# V2.net
KiCad netlist of a schematic drawn in Altium Designer
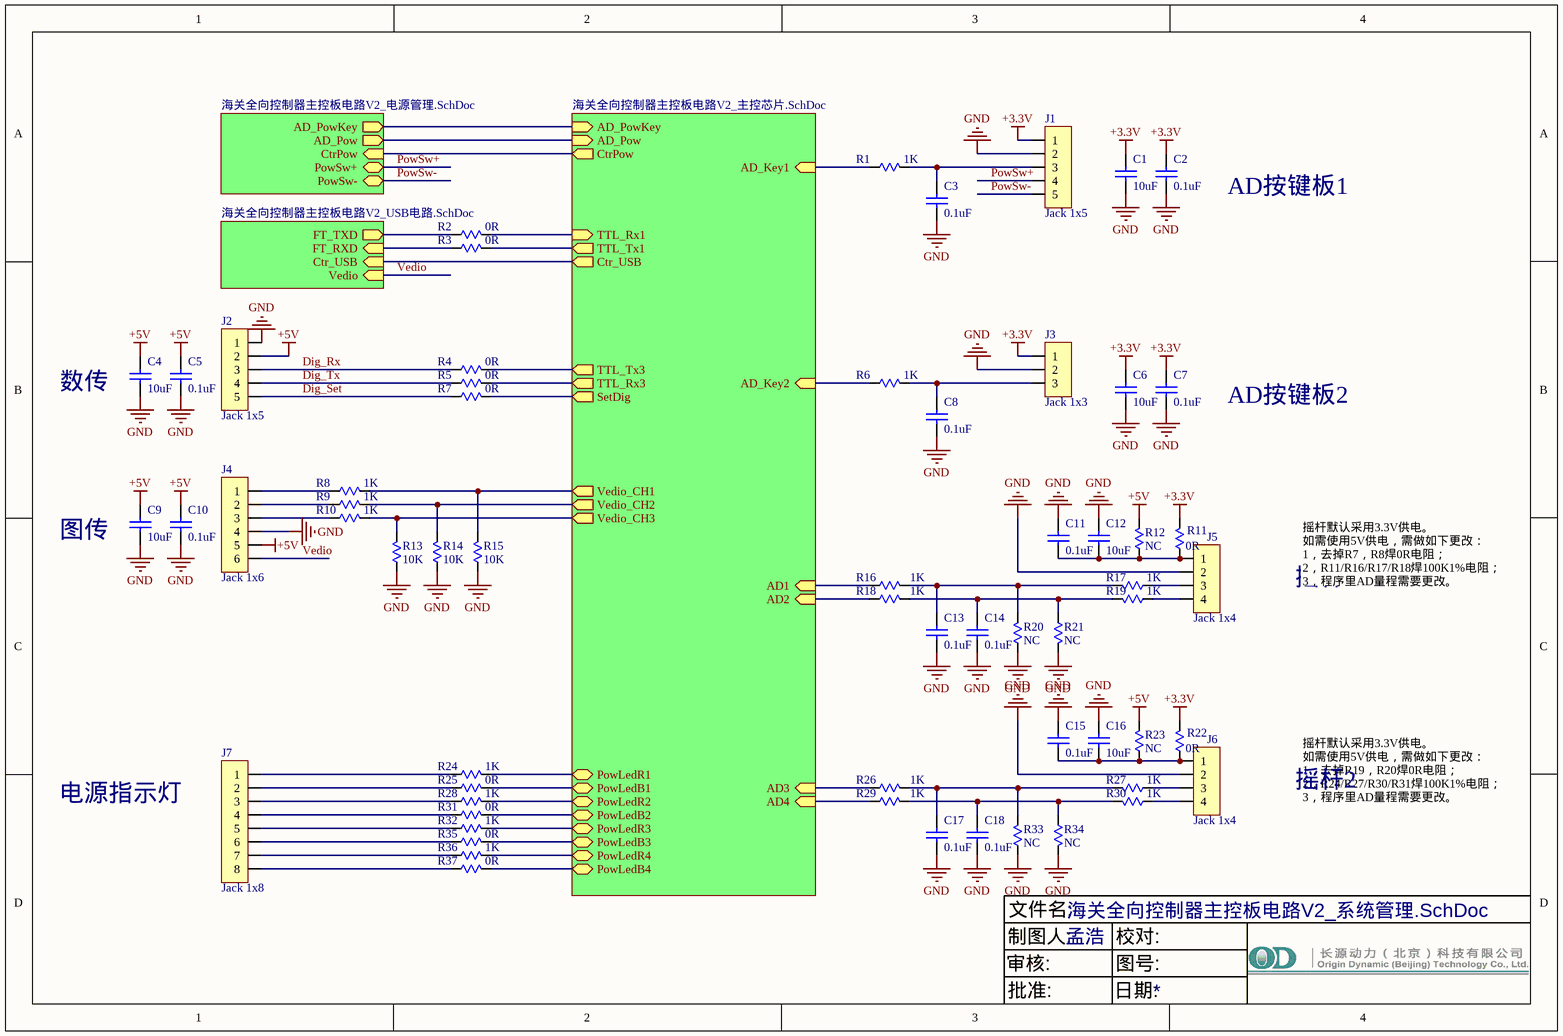
[diagram p0: 海关全向控制器主控板电路V2_系统管理.SchDoc]

(export (version "E")
  (design (tool "Eeschema 10.0.6"))
  (components
    (comp (ref "C1")
      (value "10uF")
      (footprint "C0603")
      (description "Capacitor")
      (fields (field (name "PUBLISHER") "Altium Limited"))
      (libsource (lib "Miscellaneous Devices") (part "Cap"))
    )
    (comp (ref "C2")
      (value "0.1uF")
      (footprint "C0603")
      (description "Capacitor")
      (fields (field (name "PUBLISHER") "Altium Limited"))
      (libsource (lib "Miscellaneous Devices") (part "Cap"))
    )
    (comp (ref "C3")
      (value "0.1uF")
      (footprint "C0603")
      (description "Capacitor")
      (fields (field (name "PUBLISHER") "Altium Limited"))
      (libsource (lib "Miscellaneous Devices") (part "Cap"))
    )
    (comp (ref "C4")
      (value "10uF")
      (footprint "C0603")
      (description "Capacitor")
      (fields (field (name "PUBLISHER") "Altium Limited"))
      (libsource (lib "Miscellaneous Devices") (part "Cap"))
    )
    (comp (ref "C5")
      (value "0.1uF")
      (footprint "C0603")
      (description "Capacitor")
      (fields (field (name "PUBLISHER") "Altium Limited"))
      (libsource (lib "Miscellaneous Devices") (part "Cap"))
    )
    (comp (ref "C6")
      (value "10uF")
      (footprint "C0603")
      (description "Capacitor")
      (fields (field (name "PUBLISHER") "Altium Limited"))
      (libsource (lib "Miscellaneous Devices") (part "Cap"))
    )
    (comp (ref "C7")
      (value "0.1uF")
      (footprint "C0603")
      (description "Capacitor")
      (fields (field (name "PUBLISHER") "Altium Limited"))
      (libsource (lib "Miscellaneous Devices") (part "Cap"))
    )
    (comp (ref "C8")
      (value "0.1uF")
      (footprint "C0603")
      (description "Capacitor")
      (fields (field (name "PUBLISHER") "Altium Limited"))
      (libsource (lib "Miscellaneous Devices") (part "Cap"))
    )
    (comp (ref "C9")
      (value "10uF")
      (footprint "C0603")
      (description "Capacitor")
      (fields (field (name "PUBLISHER") "Altium Limited"))
      (libsource (lib "Miscellaneous Devices") (part "Cap"))
    )
    (comp (ref "C10")
      (value "0.1uF")
      (footprint "C0603")
      (description "Capacitor")
      (fields (field (name "PUBLISHER") "Altium Limited"))
      (libsource (lib "Miscellaneous Devices") (part "Cap"))
    )
    (comp (ref "C11")
      (value "0.1uF")
      (footprint "C0603")
      (description "Capacitor")
      (fields (field (name "PUBLISHER") "Altium Limited"))
      (libsource (lib "Miscellaneous Devices") (part "Cap"))
    )
    (comp (ref "C12")
      (value "10uF")
      (footprint "C0603")
      (description "Capacitor")
      (fields (field (name "PUBLISHER") "Altium Limited"))
      (libsource (lib "Miscellaneous Devices") (part "Cap"))
    )
    (comp (ref "C13")
      (value "0.1uF")
      (footprint "C0603")
      (description "Capacitor")
      (fields (field (name "PUBLISHER") "Altium Limited"))
      (libsource (lib "Miscellaneous Devices") (part "Cap"))
    )
    (comp (ref "C14")
      (value "0.1uF")
      (footprint "C0603")
      (description "Capacitor")
      (fields (field (name "PUBLISHER") "Altium Limited"))
      (libsource (lib "Miscellaneous Devices") (part "Cap"))
    )
    (comp (ref "C15")
      (value "0.1uF")
      (footprint "C0603")
      (description "Capacitor")
      (fields (field (name "PUBLISHER") "Altium Limited"))
      (libsource (lib "Miscellaneous Devices") (part "Cap"))
    )
    (comp (ref "C16")
      (value "10uF")
      (footprint "C0603")
      (description "Capacitor")
      (fields (field (name "PUBLISHER") "Altium Limited"))
      (libsource (lib "Miscellaneous Devices") (part "Cap"))
    )
    (comp (ref "C17")
      (value "0.1uF")
      (footprint "C0603")
      (description "Capacitor")
      (fields (field (name "PUBLISHER") "Altium Limited"))
      (libsource (lib "Miscellaneous Devices") (part "Cap"))
    )
    (comp (ref "C18")
      (value "0.1uF")
      (footprint "C0603")
      (description "Capacitor")
      (fields (field (name "PUBLISHER") "Altium Limited"))
      (libsource (lib "Miscellaneous Devices") (part "Cap"))
    )
    (comp (ref "J1")
      (value "Jack 1x5")
      (footprint "ZH-5AWD")
      (description "插座")
      (libsource (lib "Connector") (part "Jack 1x5"))
    )
    (comp (ref "J2")
      (value "Jack 1x5")
      (footprint "ZH-5AWD")
      (description "插座")
      (libsource (lib "") (part "Jack 1x5_1"))
    )
    (comp (ref "J3")
      (value "Jack 1x3")
      (footprint "ZH-3AWD")
      (description "插座")
      (libsource (lib "Connector") (part "Jack 1x3"))
    )
    (comp (ref "J4")
      (value "Jack 1x6")
      (footprint "ZH-6AWD")
      (description "插座")
      (libsource (lib "Connector") (part "Jack 1x6"))
    )
    (comp (ref "J5")
      (value "Jack 1x4")
      (footprint "ZH-4AWD")
      (description "插座")
      (libsource (lib "Connector") (part "Jack 1x4"))
    )
    (comp (ref "J6")
      (value "Jack 1x4")
      (footprint "ZH-4AWD")
      (description "插座")
      (libsource (lib "Connector") (part "Jack 1x4"))
    )
    (comp (ref "J7")
      (value "Jack 1x8")
      (footprint "ZH-8AWD")
      (description "插座")
      (libsource (lib "Connector") (part "Jack 1x8"))
    )
    (comp (ref "R1")
      (value "1K")
      (footprint "R0603")
      (description "Resistor")
      (fields (field (name "PUBLISHER") "Altium Limited"))
      (libsource (lib "UP-Robot") (part "Res"))
    )
    (comp (ref "R2")
      (value "0R")
      (footprint "R0603")
      (description "Resistor")
      (fields (field (name "PUBLISHER") "Altium Limited"))
      (libsource (lib "Temp") (part "Res"))
    )
    (comp (ref "R3")
      (value "0R")
      (footprint "R0603")
      (description "Resistor")
      (fields (field (name "PUBLISHER") "Altium Limited"))
      (libsource (lib "Temp") (part "Res"))
    )
    (comp (ref "R4")
      (value "0R")
      (footprint "R0603")
      (description "Resistor")
      (fields (field (name "PUBLISHER") "Altium Limited"))
      (libsource (lib "UP-Robot") (part "Res"))
    )
    (comp (ref "R5")
      (value "0R")
      (footprint "R0603")
      (description "Resistor")
      (fields (field (name "PUBLISHER") "Altium Limited"))
      (libsource (lib "UP-Robot") (part "Res"))
    )
    (comp (ref "R6")
      (value "1K")
      (footprint "R0603")
      (description "Resistor")
      (fields (field (name "PUBLISHER") "Altium Limited"))
      (libsource (lib "UP-Robot") (part "Res"))
    )
    (comp (ref "R7")
      (value "0R")
      (footprint "R0603")
      (description "Resistor")
      (fields (field (name "PUBLISHER") "Altium Limited"))
      (libsource (lib "UP-Robot") (part "Res"))
    )
    (comp (ref "R8")
      (value "1K")
      (footprint "R0603")
      (description "Resistor")
      (fields (field (name "PUBLISHER") "Altium Limited"))
      (libsource (lib "UP-Robot") (part "Res"))
    )
    (comp (ref "R9")
      (value "1K")
      (footprint "R0603")
      (description "Resistor")
      (fields (field (name "PUBLISHER") "Altium Limited"))
      (libsource (lib "UP-Robot") (part "Res"))
    )
    (comp (ref "R10")
      (value "1K")
      (footprint "R0603")
      (description "Resistor")
      (fields (field (name "PUBLISHER") "Altium Limited"))
      (libsource (lib "UP-Robot") (part "Res"))
    )
    (comp (ref "R11")
      (value "0R")
      (footprint "R0603")
      (description "Resistor")
      (fields (field (name "PUBLISHER") "Altium Limited"))
      (libsource (lib "UP-Robot") (part "Res"))
    )
    (comp (ref "R12")
      (value "NC")
      (footprint "R0603")
      (description "Resistor")
      (fields (field (name "PUBLISHER") "Altium Limited"))
      (libsource (lib "UP-Robot") (part "Res"))
    )
    (comp (ref "R13")
      (value "10K")
      (footprint "R0603")
      (description "Resistor")
      (fields (field (name "PUBLISHER") "Altium Limited"))
      (libsource (lib "UP-Robot") (part "Res"))
    )
    (comp (ref "R14")
      (value "10K")
      (footprint "R0603")
      (description "Resistor")
      (fields (field (name "PUBLISHER") "Altium Limited"))
      (libsource (lib "UP-Robot") (part "Res"))
    )
    (comp (ref "R15")
      (value "10K")
      (footprint "R0603")
      (description "Resistor")
      (fields (field (name "PUBLISHER") "Altium Limited"))
      (libsource (lib "UP-Robot") (part "Res"))
    )
    (comp (ref "R16")
      (value "1K")
      (footprint "R0603")
      (description "Resistor")
      (fields (field (name "PUBLISHER") "Altium Limited"))
      (libsource (lib "UP-Robot") (part "Res"))
    )
    (comp (ref "R17")
      (value "1K")
      (footprint "R0603")
      (description "Resistor")
      (fields (field (name "PUBLISHER") "Altium Limited"))
      (libsource (lib "UP-Robot") (part "Res"))
    )
    (comp (ref "R18")
      (value "1K")
      (footprint "R0603")
      (description "Resistor")
      (fields (field (name "PUBLISHER") "Altium Limited"))
      (libsource (lib "UP-Robot") (part "Res"))
    )
    (comp (ref "R19")
      (value "1K")
      (footprint "R0603")
      (description "Resistor")
      (fields (field (name "PUBLISHER") "Altium Limited"))
      (libsource (lib "UP-Robot") (part "Res"))
    )
    (comp (ref "R20")
      (value "NC")
      (footprint "R0603")
      (description "Resistor")
      (fields (field (name "PUBLISHER") "Altium Limited"))
      (libsource (lib "UP-Robot") (part "Res"))
    )
    (comp (ref "R21")
      (value "NC")
      (footprint "R0603")
      (description "Resistor")
      (fields (field (name "PUBLISHER") "Altium Limited"))
      (libsource (lib "UP-Robot") (part "Res"))
    )
    (comp (ref "R22")
      (value "0R")
      (footprint "R0603")
      (description "Resistor")
      (fields (field (name "PUBLISHER") "Altium Limited"))
      (libsource (lib "UP-Robot") (part "Res"))
    )
    (comp (ref "R23")
      (value "NC")
      (footprint "R0603")
      (description "Resistor")
      (fields (field (name "PUBLISHER") "Altium Limited"))
      (libsource (lib "UP-Robot") (part "Res"))
    )
    (comp (ref "R24")
      (value "1K")
      (footprint "R0603")
      (description "Resistor")
      (fields (field (name "PUBLISHER") "Altium Limited"))
      (libsource (lib "UP-Robot") (part "Res"))
    )
    (comp (ref "R25")
      (value "0R")
      (footprint "R0603")
      (description "Resistor")
      (fields (field (name "PUBLISHER") "Altium Limited"))
      (libsource (lib "UP-Robot") (part "Res"))
    )
    (comp (ref "R26")
      (value "1K")
      (footprint "R0603")
      (description "Resistor")
      (fields (field (name "PUBLISHER") "Altium Limited"))
      (libsource (lib "UP-Robot") (part "Res"))
    )
    (comp (ref "R27")
      (value "1K")
      (footprint "R0603")
      (description "Resistor")
      (fields (field (name "PUBLISHER") "Altium Limited"))
      (libsource (lib "UP-Robot") (part "Res"))
    )
    (comp (ref "R28")
      (value "1K")
      (footprint "R0603")
      (description "Resistor")
      (fields (field (name "PUBLISHER") "Altium Limited"))
      (libsource (lib "UP-Robot") (part "Res"))
    )
    (comp (ref "R29")
      (value "1K")
      (footprint "R0603")
      (description "Resistor")
      (fields (field (name "PUBLISHER") "Altium Limited"))
      (libsource (lib "UP-Robot") (part "Res"))
    )
    (comp (ref "R30")
      (value "1K")
      (footprint "R0603")
      (description "Resistor")
      (fields (field (name "PUBLISHER") "Altium Limited"))
      (libsource (lib "UP-Robot") (part "Res"))
    )
    (comp (ref "R31")
      (value "0R")
      (footprint "R0603")
      (description "Resistor")
      (fields (field (name "PUBLISHER") "Altium Limited"))
      (libsource (lib "UP-Robot") (part "Res"))
    )
    (comp (ref "R32")
      (value "1K")
      (footprint "R0603")
      (description "Resistor")
      (fields (field (name "PUBLISHER") "Altium Limited"))
      (libsource (lib "UP-Robot") (part "Res"))
    )
    (comp (ref "R33")
      (value "NC")
      (footprint "R0603")
      (description "Resistor")
      (fields (field (name "PUBLISHER") "Altium Limited"))
      (libsource (lib "UP-Robot") (part "Res"))
    )
    (comp (ref "R34")
      (value "NC")
      (footprint "R0603")
      (description "Resistor")
      (fields (field (name "PUBLISHER") "Altium Limited"))
      (libsource (lib "UP-Robot") (part "Res"))
    )
    (comp (ref "R35")
      (value "0R")
      (footprint "R0603")
      (description "Resistor")
      (fields (field (name "PUBLISHER") "Altium Limited"))
      (libsource (lib "UP-Robot") (part "Res"))
    )
    (comp (ref "R36")
      (value "1K")
      (footprint "R0603")
      (description "Resistor")
      (fields (field (name "PUBLISHER") "Altium Limited"))
      (libsource (lib "UP-Robot") (part "Res"))
    )
    (comp (ref "R37")
      (value "0R")
      (footprint "R0603")
      (description "Resistor")
      (fields (field (name "PUBLISHER") "Altium Limited"))
      (libsource (lib "UP-Robot") (part "Res"))
    )
  )
  (nets
    (net (code "1") (name "+3.3V") (class "Default")
      (node (ref "C1") (pin "1") (pinfunction "1_1") (pintype "passive"))
      (node (ref "C2") (pin "1") (pinfunction "1_1") (pintype "passive"))
      (node (ref "C6") (pin "1") (pinfunction "1_1") (pintype "passive"))
      (node (ref "C7") (pin "1") (pinfunction "1_1") (pintype "passive"))
      (node (ref "J1") (pin "1") (pinfunction "1_1") (pintype "passive"))
      (node (ref "J3") (pin "1") (pinfunction "1_1") (pintype "passive"))
      (node (ref "R11") (pin "1") (pinfunction "1_1") (pintype "passive"))
      (node (ref "R22") (pin "1") (pinfunction "1_1") (pintype "passive"))
    )
    (net (code "2") (name "+5V") (class "Default")
      (node (ref "C10") (pin "1") (pinfunction "1_1") (pintype "passive"))
      (node (ref "C4") (pin "1") (pinfunction "1_1") (pintype "passive"))
      (node (ref "C5") (pin "1") (pinfunction "1_1") (pintype "passive"))
      (node (ref "C9") (pin "1") (pinfunction "1_1") (pintype "passive"))
      (node (ref "J2") (pin "2") (pinfunction "2_2") (pintype "passive"))
      (node (ref "J4") (pin "5") (pinfunction "5_5") (pintype "passive"))
      (node (ref "R12") (pin "1") (pinfunction "1_1") (pintype "passive"))
      (node (ref "R23") (pin "1") (pinfunction "1_1") (pintype "passive"))
    )
    (net (code "3") (name "/AD1") (class "Default")
      (node (ref "R16") (pin "2") (pinfunction "2_2") (pintype "passive"))
    )
    (net (code "4") (name "/AD2") (class "Default")
      (node (ref "R18") (pin "2") (pinfunction "2_2") (pintype "passive"))
    )
    (net (code "5") (name "/AD3") (class "Default")
      (node (ref "R26") (pin "2") (pinfunction "2_2") (pintype "passive"))
    )
    (net (code "6") (name "/AD4") (class "Default")
      (node (ref "R29") (pin "2") (pinfunction "2_2") (pintype "passive"))
    )
    (net (code "7") (name "/AD_Key1") (class "Default")
      (node (ref "R1") (pin "1") (pinfunction "1_1") (pintype "passive"))
    )
    (net (code "8") (name "/AD_Key2") (class "Default")
      (node (ref "R6") (pin "1") (pinfunction "1_1") (pintype "passive"))
    )
    (net (code "13") (name "/Dig_Rx") (class "Default")
      (node (ref "J2") (pin "3") (pinfunction "3_3") (pintype "passive"))
      (node (ref "R4") (pin "1") (pinfunction "1_1") (pintype "passive"))
    )
    (net (code "14") (name "/Dig_Set") (class "Default")
      (node (ref "J2") (pin "5") (pinfunction "5_5") (pintype "passive"))
      (node (ref "R7") (pin "1") (pinfunction "1_1") (pintype "passive"))
    )
    (net (code "15") (name "/Dig_Tx") (class "Default")
      (node (ref "J2") (pin "4") (pinfunction "4_4") (pintype "passive"))
      (node (ref "R5") (pin "1") (pinfunction "1_1") (pintype "passive"))
    )
    (net (code "16") (name "/FT_RXD") (class "Default")
      (node (ref "R3") (pin "2") (pinfunction "2_2") (pintype "passive"))
    )
    (net (code "17") (name "/FT_TXD") (class "Default")
      (node (ref "R2") (pin "2") (pinfunction "2_2") (pintype "passive"))
    )
    (net (code "18") (name "/PowLedB1") (class "Default")
      (node (ref "R25") (pin "2") (pinfunction "2_2") (pintype "passive"))
    )
    (net (code "19") (name "/PowLedB2") (class "Default")
      (node (ref "R31") (pin "2") (pinfunction "2_2") (pintype "passive"))
    )
    (net (code "20") (name "/PowLedB3") (class "Default")
      (node (ref "R35") (pin "2") (pinfunction "2_2") (pintype "passive"))
    )
    (net (code "21") (name "/PowLedB4") (class "Default")
      (node (ref "R37") (pin "2") (pinfunction "2_2") (pintype "passive"))
    )
    (net (code "22") (name "/PowLedR1") (class "Default")
      (node (ref "R24") (pin "2") (pinfunction "2_2") (pintype "passive"))
    )
    (net (code "23") (name "/PowLedR2") (class "Default")
      (node (ref "R28") (pin "2") (pinfunction "2_2") (pintype "passive"))
    )
    (net (code "24") (name "/PowLedR3") (class "Default")
      (node (ref "R32") (pin "2") (pinfunction "2_2") (pintype "passive"))
    )
    (net (code "25") (name "/PowLedR4") (class "Default")
      (node (ref "R36") (pin "2") (pinfunction "2_2") (pintype "passive"))
    )
    (net (code "26") (name "/PowSw+") (class "Default")
      (node (ref "J1") (pin "4") (pinfunction "4_4") (pintype "passive"))
    )
    (net (code "27") (name "/PowSw-") (class "Default")
      (node (ref "J1") (pin "5") (pinfunction "5_5") (pintype "passive"))
    )
    (net (code "28") (name "/SetDig") (class "Default")
      (node (ref "R7") (pin "2") (pinfunction "2_2") (pintype "passive"))
    )
    (net (code "29") (name "/TTL_Rx1") (class "Default")
      (node (ref "R2") (pin "1") (pinfunction "1_1") (pintype "passive"))
    )
    (net (code "30") (name "/TTL_Rx3") (class "Default")
      (node (ref "R5") (pin "2") (pinfunction "2_2") (pintype "passive"))
    )
    (net (code "31") (name "/TTL_Tx1") (class "Default")
      (node (ref "R3") (pin "1") (pinfunction "1_1") (pintype "passive"))
    )
    (net (code "32") (name "/TTL_Tx3") (class "Default")
      (node (ref "R4") (pin "2") (pinfunction "2_2") (pintype "passive"))
    )
    (net (code "33") (name "/Vedio") (class "Default")
      (node (ref "J4") (pin "6") (pinfunction "6_6") (pintype "passive"))
    )
    (net (code "34") (name "/Vedio_CH1") (class "Default")
      (node (ref "R15") (pin "2") (pinfunction "2_2") (pintype "passive"))
      (node (ref "R8") (pin "2") (pinfunction "2_2") (pintype "passive"))
    )
    (net (code "35") (name "/Vedio_CH2") (class "Default")
      (node (ref "R14") (pin "2") (pinfunction "2_2") (pintype "passive"))
      (node (ref "R9") (pin "2") (pinfunction "2_2") (pintype "passive"))
    )
    (net (code "36") (name "/Vedio_CH3") (class "Default")
      (node (ref "R10") (pin "2") (pinfunction "2_2") (pintype "passive"))
      (node (ref "R13") (pin "2") (pinfunction "2_2") (pintype "passive"))
    )
    (net (code "37") (name "GND") (class "Default")
      (node (ref "C1") (pin "2") (pinfunction "2_2") (pintype "passive"))
      (node (ref "C10") (pin "2") (pinfunction "2_2") (pintype "passive"))
      (node (ref "C11") (pin "1") (pinfunction "1_1") (pintype "passive"))
      (node (ref "C12") (pin "1") (pinfunction "1_1") (pintype "passive"))
      (node (ref "C13") (pin "2") (pinfunction "2_2") (pintype "passive"))
      (node (ref "C14") (pin "2") (pinfunction "2_2") (pintype "passive"))
      (node (ref "C15") (pin "1") (pinfunction "1_1") (pintype "passive"))
      (node (ref "C16") (pin "1") (pinfunction "1_1") (pintype "passive"))
      (node (ref "C17") (pin "2") (pinfunction "2_2") (pintype "passive"))
      (node (ref "C18") (pin "2") (pinfunction "2_2") (pintype "passive"))
      (node (ref "C2") (pin "2") (pinfunction "2_2") (pintype "passive"))
      (node (ref "C3") (pin "2") (pinfunction "2_2") (pintype "passive"))
      (node (ref "C4") (pin "2") (pinfunction "2_2") (pintype "passive"))
      (node (ref "C5") (pin "2") (pinfunction "2_2") (pintype "passive"))
      (node (ref "C6") (pin "2") (pinfunction "2_2") (pintype "passive"))
      (node (ref "C7") (pin "2") (pinfunction "2_2") (pintype "passive"))
      (node (ref "C8") (pin "2") (pinfunction "2_2") (pintype "passive"))
      (node (ref "C9") (pin "2") (pinfunction "2_2") (pintype "passive"))
      (node (ref "J1") (pin "2") (pinfunction "2_2") (pintype "passive"))
      (node (ref "J2") (pin "1") (pinfunction "1_1") (pintype "passive"))
      (node (ref "J3") (pin "2") (pinfunction "2_2") (pintype "passive"))
      (node (ref "J4") (pin "4") (pinfunction "4_4") (pintype "passive"))
      (node (ref "J5") (pin "2") (pinfunction "2_2") (pintype "passive"))
      (node (ref "J6") (pin "2") (pinfunction "2_2") (pintype "passive"))
      (node (ref "R13") (pin "1") (pinfunction "1_1") (pintype "passive"))
      (node (ref "R14") (pin "1") (pinfunction "1_1") (pintype "passive"))
      (node (ref "R15") (pin "1") (pinfunction "1_1") (pintype "passive"))
      (node (ref "R20") (pin "2") (pinfunction "2_2") (pintype "passive"))
      (node (ref "R21") (pin "1") (pinfunction "1_1") (pintype "passive"))
      (node (ref "R33") (pin "2") (pinfunction "2_2") (pintype "passive"))
      (node (ref "R34") (pin "1") (pinfunction "1_1") (pintype "passive"))
    )
    (net (code "38") (name "Net-(C3-Pad1)") (class "Default")
      (node (ref "C3") (pin "1") (pinfunction "1_1") (pintype "passive"))
      (node (ref "J1") (pin "3") (pinfunction "3_3") (pintype "passive"))
      (node (ref "R1") (pin "2") (pinfunction "2_2") (pintype "passive"))
    )
    (net (code "39") (name "Net-(C8-Pad1)") (class "Default")
      (node (ref "C8") (pin "1") (pinfunction "1_1") (pintype "passive"))
      (node (ref "J3") (pin "3") (pinfunction "3_3") (pintype "passive"))
      (node (ref "R6") (pin "2") (pinfunction "2_2") (pintype "passive"))
    )
    (net (code "40") (name "Net-(C11-Pad2)") (class "Default")
      (node (ref "C11") (pin "2") (pinfunction "2_2") (pintype "passive"))
      (node (ref "C12") (pin "2") (pinfunction "2_2") (pintype "passive"))
      (node (ref "J5") (pin "1") (pinfunction "1_1") (pintype "passive"))
      (node (ref "R11") (pin "2") (pinfunction "2_2") (pintype "passive"))
      (node (ref "R12") (pin "2") (pinfunction "2_2") (pintype "passive"))
    )
    (net (code "41") (name "Net-(C13-Pad1)") (class "Default")
      (node (ref "C13") (pin "1") (pinfunction "1_1") (pintype "passive"))
      (node (ref "R16") (pin "1") (pinfunction "1_1") (pintype "passive"))
      (node (ref "R17") (pin "1") (pinfunction "1_1") (pintype "passive"))
      (node (ref "R20") (pin "1") (pinfunction "1_1") (pintype "passive"))
    )
    (net (code "42") (name "Net-(C14-Pad1)") (class "Default")
      (node (ref "C14") (pin "1") (pinfunction "1_1") (pintype "passive"))
      (node (ref "R18") (pin "1") (pinfunction "1_1") (pintype "passive"))
      (node (ref "R19") (pin "1") (pinfunction "1_1") (pintype "passive"))
      (node (ref "R21") (pin "2") (pinfunction "2_2") (pintype "passive"))
    )
    (net (code "43") (name "Net-(C15-Pad2)") (class "Default")
      (node (ref "C15") (pin "2") (pinfunction "2_2") (pintype "passive"))
      (node (ref "C16") (pin "2") (pinfunction "2_2") (pintype "passive"))
      (node (ref "J6") (pin "1") (pinfunction "1_1") (pintype "passive"))
      (node (ref "R22") (pin "2") (pinfunction "2_2") (pintype "passive"))
      (node (ref "R23") (pin "2") (pinfunction "2_2") (pintype "passive"))
    )
    (net (code "44") (name "Net-(C17-Pad1)") (class "Default")
      (node (ref "C17") (pin "1") (pinfunction "1_1") (pintype "passive"))
      (node (ref "R26") (pin "1") (pinfunction "1_1") (pintype "passive"))
      (node (ref "R27") (pin "1") (pinfunction "1_1") (pintype "passive"))
      (node (ref "R33") (pin "1") (pinfunction "1_1") (pintype "passive"))
    )
    (net (code "45") (name "Net-(C18-Pad1)") (class "Default")
      (node (ref "C18") (pin "1") (pinfunction "1_1") (pintype "passive"))
      (node (ref "R29") (pin "1") (pinfunction "1_1") (pintype "passive"))
      (node (ref "R30") (pin "1") (pinfunction "1_1") (pintype "passive"))
      (node (ref "R34") (pin "2") (pinfunction "2_2") (pintype "passive"))
    )
    (net (code "46") (name "Net-(J4-Pad1)") (class "Default")
      (node (ref "J4") (pin "1") (pinfunction "1_1") (pintype "passive"))
      (node (ref "R8") (pin "1") (pinfunction "1_1") (pintype "passive"))
    )
    (net (code "47") (name "Net-(J4-Pad2)") (class "Default")
      (node (ref "J4") (pin "2") (pinfunction "2_2") (pintype "passive"))
      (node (ref "R9") (pin "1") (pinfunction "1_1") (pintype "passive"))
    )
    (net (code "48") (name "Net-(J4-Pad3)") (class "Default")
      (node (ref "J4") (pin "3") (pinfunction "3_3") (pintype "passive"))
      (node (ref "R10") (pin "1") (pinfunction "1_1") (pintype "passive"))
    )
    (net (code "49") (name "Net-(J5-Pad3)") (class "Default")
      (node (ref "J5") (pin "3") (pinfunction "3_3") (pintype "passive"))
      (node (ref "R17") (pin "2") (pinfunction "2_2") (pintype "passive"))
    )
    (net (code "50") (name "Net-(J5-Pad4)") (class "Default")
      (node (ref "J5") (pin "4") (pinfunction "4_4") (pintype "passive"))
      (node (ref "R19") (pin "2") (pinfunction "2_2") (pintype "passive"))
    )
    (net (code "51") (name "Net-(J6-Pad3)") (class "Default")
      (node (ref "J6") (pin "3") (pinfunction "3_3") (pintype "passive"))
      (node (ref "R27") (pin "2") (pinfunction "2_2") (pintype "passive"))
    )
    (net (code "52") (name "Net-(J6-Pad4)") (class "Default")
      (node (ref "J6") (pin "4") (pinfunction "4_4") (pintype "passive"))
      (node (ref "R30") (pin "2") (pinfunction "2_2") (pintype "passive"))
    )
    (net (code "53") (name "Net-(J7-Pad1)") (class "Default")
      (node (ref "J7") (pin "1") (pinfunction "1_1") (pintype "passive"))
      (node (ref "R24") (pin "1") (pinfunction "1_1") (pintype "passive"))
    )
    (net (code "54") (name "Net-(J7-Pad2)") (class "Default")
      (node (ref "J7") (pin "2") (pinfunction "2_2") (pintype "passive"))
      (node (ref "R25") (pin "1") (pinfunction "1_1") (pintype "passive"))
    )
    (net (code "55") (name "Net-(J7-Pad3)") (class "Default")
      (node (ref "J7") (pin "3") (pinfunction "3_3") (pintype "passive"))
      (node (ref "R28") (pin "1") (pinfunction "1_1") (pintype "passive"))
    )
    (net (code "56") (name "Net-(J7-Pad4)") (class "Default")
      (node (ref "J7") (pin "4") (pinfunction "4_4") (pintype "passive"))
      (node (ref "R31") (pin "1") (pinfunction "1_1") (pintype "passive"))
    )
    (net (code "57") (name "Net-(J7-Pad5)") (class "Default")
      (node (ref "J7") (pin "5") (pinfunction "5_5") (pintype "passive"))
      (node (ref "R32") (pin "1") (pinfunction "1_1") (pintype "passive"))
    )
    (net (code "58") (name "Net-(J7-Pad6)") (class "Default")
      (node (ref "J7") (pin "6") (pinfunction "6_6") (pintype "passive"))
      (node (ref "R35") (pin "1") (pinfunction "1_1") (pintype "passive"))
    )
    (net (code "59") (name "Net-(J7-Pad7)") (class "Default")
      (node (ref "J7") (pin "7") (pinfunction "7_7") (pintype "passive"))
      (node (ref "R36") (pin "1") (pinfunction "1_1") (pintype "passive"))
    )
    (net (code "60") (name "Net-(J7-Pad8)") (class "Default")
      (node (ref "J7") (pin "8") (pinfunction "8_8") (pintype "passive"))
      (node (ref "R37") (pin "1") (pinfunction "1_1") (pintype "passive"))
    )
  )
)
